# SH3_-_19V_BUCK_CONVERTER.net
KiCad netlist of a schematic drawn in Altium Designer
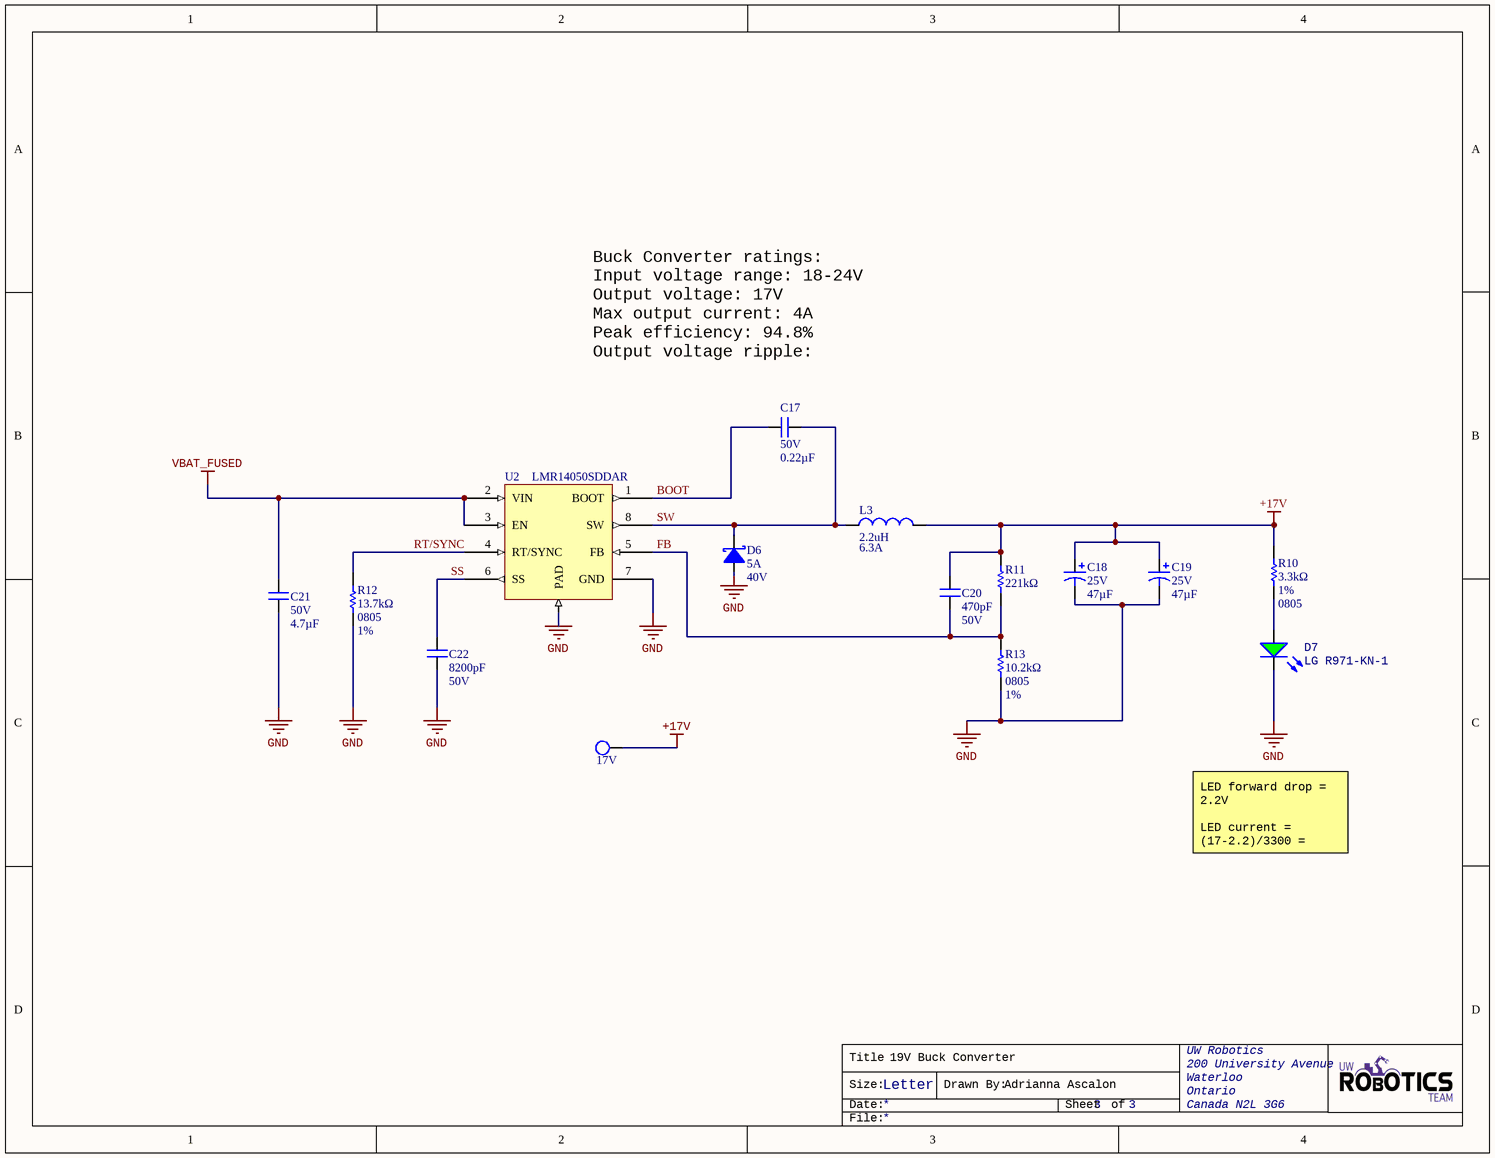
[diagram p0: SH3 - 19V BUCK CONVERTER.SchDoc]

(export (version "E")
  (design (tool "Eeschema 10.0.6"))
  (components
    (comp (ref "17V")
      (value "TESTPOINT_LOOP")
      (footprint "TESTPOINT_LOOP")
      (description "PC TEST POINT MINIATURE WHITE")
      (libsource (lib "UWRT_Schematic_Library_2020") (part "TESTPOINT_LOOP"))
    )
    (comp (ref "C17")
      (value "GRM21BR71H224MA01L")
      (footprint "CAP 0805_2012")
      (description "CAP CER 0.22UF 50V X7R 0805")
      (fields
        (field (name "TOLERANCE") "20%")
        (field (name "VOLTAGE RATING") "50V")
        (field (name "CAPACITANCE") "0.22µF")
      )
      (libsource (lib "UWRT_Schematic_Library_2020") (part "GRM21BR71H224MA01L"))
    )
    (comp (ref "C18")
      (value "47μF")
      (footprint "25SVPF47M")
      (description "CAP ALUM POLY 47UF 20% 25V SMD")
      (fields
        (field (name "TOLERANCE") "20%")
        (field (name "VOLTAGE") "25V")
        (field (name "CAPACITANCE") "47µF")
      )
      (libsource (lib "UWRT_Schematic_Library_2020") (part "25SVPF47M"))
    )
    (comp (ref "C19")
      (value "47μF")
      (footprint "25SVPF47M")
      (description "CAP ALUM POLY 47UF 20% 25V SMD")
      (fields
        (field (name "TOLERANCE") "20%")
        (field (name "VOLTAGE") "25V")
        (field (name "CAPACITANCE") "47µF")
      )
      (libsource (lib "UWRT_Schematic_Library_2020") (part "25SVPF47M"))
    )
    (comp (ref "C20")
      (value "470pF")
      (footprint "CAP 0805_2012")
      (description "CAP CER 470PF 50V X7R 0805")
      (fields (field (name "VOLTAGE RATING") "50V") (field (name "TOLERANCE") "5%"))
      (libsource (lib "UWRT_Schematic_Library_2020") (part "CAP_470pF_50V_0805"))
    )
    (comp (ref "C21")
      (value "GRM31CR71H475KA12L")
      (footprint "CAPC1206(3216)")
      (description "CAP CER 4.7UF 50V X7R 1206")
      (fields
        (field (name "TOLERANCE") "10%")
        (field (name "VOLTAGE") "50V")
        (field (name "VOLTAGE RATING") "50V")
        (field (name "CAPACITANCE") "4.7µF")
      )
      (libsource (lib "UWRT_Schematic_Library_2020") (part "GRM31CR71H475KA12L"))
    )
    (comp (ref "C22")
      (value "8200pF")
      (footprint "CAP 0805_2012")
      (description "CAP CER 8200PF 50V X7R 0805")
      (fields (field (name "TOLERANCE") "10%") (field (name "VOLTAGE RATING") "50V"))
      (libsource (lib "UWRT_Schematic_Library_2020") (part "CAP_8200pF_50V_0805"))
    )
    (comp (ref "D6")
      (value "B540C-13-F")
      (footprint "DO214AB SMC")
      (description "DIODE SCHOTTKY 40V 5A SMC")
      (fields (field (name "FORWARD CURRENT") "5A") (field (name "VOLTAGE") "40V"))
      (libsource (lib "UWRT_Schematic_Library_2020") (part "B540C-13-F"))
    )
    (comp (ref "D7")
      (value "LG R971-KN-1")
      (footprint "LED_0805_LINE")
      (description "LED GREEN DIFFUSED 0805 SMD")
      (libsource (lib "UWRT_Schematic_Library_2020") (part "DIO_LED_G"))
    )
    (comp (ref "L3")
      (value "SRN8040-2R2Y")
      (footprint "IND_BOURNS_SRN80")
      (description "FIXED IND 2.2UH 6.3A 13 MOHM SMD")
      (fields
        (field (name "TOLERANCE") "30%")
        (field (name "INDUCTANCE") "2.2uH")
        (field (name "MAX DC CURRENT") "6.3A")
      )
      (libsource (lib "UWRT_Schematic_Library_2020") (part "SRN8040-2R2Y"))
    )
    (comp (ref "R10")
      (value "3.3kΩ")
      (footprint "RESC0805(2012)_L")
      (description "RES SMD 3.3K OHM 1% 1/8W 0805")
      (fields (field (name "TOLERANCE") "1%") (field (name "CASE CODE (IMPERIAL)") "0805"))
      (libsource (lib "UWRT_Schematic_Library_2020") (part "RES_3.3kΩ_0805"))
    )
    (comp (ref "R11")
      (value "221kΩ")
      (footprint "RESC2012X60N")
      (description "RES SMD 221K OHM 1% 1/8W 0805")
      (fields (field (name "TOLERANCE") "1%"))
      (libsource (lib "UWRT_Schematic_Library_2020") (part "RES_221kΩ_0805"))
    )
    (comp (ref "R12")
      (value "13.7kΩ")
      (footprint "RESC2012X60N")
      (description "RES SMD 13.7K OHM 1% 1/8W 0805")
      (fields (field (name "CASE CODE (IMPERIAL)") "0805") (field (name "TOLERANCE") "1%"))
      (libsource (lib "UWRT_Schematic_Library_2020") (part "RES_13.7kΩ_0805"))
    )
    (comp (ref "R13")
      (value "10.2kΩ")
      (footprint "RESC2012X60N")
      (description "RES SMD 10.2K OHM 1% 1/8W 0805")
      (fields (field (name "CASE CODE (IMPERIAL)") "0805") (field (name "TOLERANCE") "1%"))
      (libsource (lib "UWRT_Schematic_Library_2020") (part "RES_10.2kΩ_0805"))
    )
    (comp (ref "U2")
      (value "LMR14050SDDAR")
      (footprint "UWRT_Footprint_Library_2020:DDA8")
      (description "Buck, 40V, 5A  2.2MHz Step-Down Regulator with 40µA IQ 8-SO PowerPAD -40 to 125")
      (libsource (lib "UWRT_Schematic_Library_2020") (part "LMR14050SDDAR"))
    )
  )
  (nets
    (net (code "1") (name "+17V") (class "Default")
      (node (ref "17V") (pin "1") (pintype "passive"))
      (node (ref "C18") (pin "1") (pinfunction "1_1") (pintype "passive"))
      (node (ref "C19") (pin "1") (pinfunction "1_1") (pintype "passive"))
      (node (ref "C20") (pin "2") (pinfunction "2_2") (pintype "passive"))
      (node (ref "L3") (pin "2") (pinfunction "2_2") (pintype "passive"))
      (node (ref "R10") (pin "2") (pinfunction "2_2") (pintype "passive"))
      (node (ref "R11") (pin "2") (pinfunction "2_2") (pintype "passive"))
    )
    (net (code "2") (name "/BOOT") (class "Default")
      (node (ref "C17") (pin "2") (pinfunction "2_2") (pintype "passive"))
      (node (ref "U2") (pin "1") (pinfunction "BOOT_1") (pintype "output"))
    )
    (net (code "3") (name "/FB") (class "Default")
      (node (ref "C20") (pin "1") (pinfunction "1_1") (pintype "passive"))
      (node (ref "R11") (pin "1") (pinfunction "1_1") (pintype "passive"))
      (node (ref "R13") (pin "2") (pinfunction "2_2") (pintype "passive"))
      (node (ref "U2") (pin "5") (pinfunction "FB_5") (pintype "input"))
    )
    (net (code "4") (name "/RT{slash}SYNC") (class "Default")
      (node (ref "R12") (pin "2") (pinfunction "2_2") (pintype "passive"))
      (node (ref "U2") (pin "4") (pinfunction "RT/SYNC_4") (pintype "input"))
    )
    (net (code "5") (name "/SS") (class "Default")
      (node (ref "C22") (pin "2") (pinfunction "2_2") (pintype "passive"))
      (node (ref "U2") (pin "6") (pinfunction "SS_6") (pintype "output"))
    )
    (net (code "6") (name "/SW") (class "Default")
      (node (ref "C17") (pin "1") (pinfunction "1_1") (pintype "passive"))
      (node (ref "D6") (pin "2") (pinfunction "Cathode_2") (pintype "passive"))
      (node (ref "L3") (pin "1") (pinfunction "1_1") (pintype "passive"))
      (node (ref "U2") (pin "8") (pinfunction "SW_8") (pintype "output"))
    )
    (net (code "7") (name "GND") (class "Default")
      (node (ref "C18") (pin "2") (pinfunction "2_2") (pintype "passive"))
      (node (ref "C19") (pin "2") (pinfunction "2_2") (pintype "passive"))
      (node (ref "C21") (pin "2") (pinfunction "2_2") (pintype "passive"))
      (node (ref "C22") (pin "1") (pinfunction "1_1") (pintype "passive"))
      (node (ref "D6") (pin "1") (pinfunction "Anode_1") (pintype "passive"))
      (node (ref "D7") (pin "2") (pinfunction "K_2") (pintype "passive"))
      (node (ref "R12") (pin "1") (pinfunction "1_1") (pintype "passive"))
      (node (ref "R13") (pin "1") (pinfunction "1_1") (pintype "passive"))
      (node (ref "U2") (pin "7") (pinfunction "GND_7") (pintype "power_in"))
      (node (ref "U2") (pin "9") (pinfunction "PAD_9") (pintype "input"))
    )
    (net (code "8") (name "Net-(D7-A)") (class "Default")
      (node (ref "D7") (pin "1") (pinfunction "A_1") (pintype "passive"))
      (node (ref "R10") (pin "1") (pinfunction "1_1") (pintype "passive"))
    )
    (net (code "9") (name "VBAT_FUSED") (class "Default")
      (node (ref "C21") (pin "1") (pinfunction "1_1") (pintype "passive"))
      (node (ref "U2") (pin "2") (pinfunction "VIN_2") (pintype "input"))
      (node (ref "U2") (pin "3") (pinfunction "EN_3") (pintype "input"))
    )
  )
)
